# Memory_Address_Register.net
KiCad netlist of a schematic drawn in Altium Designer
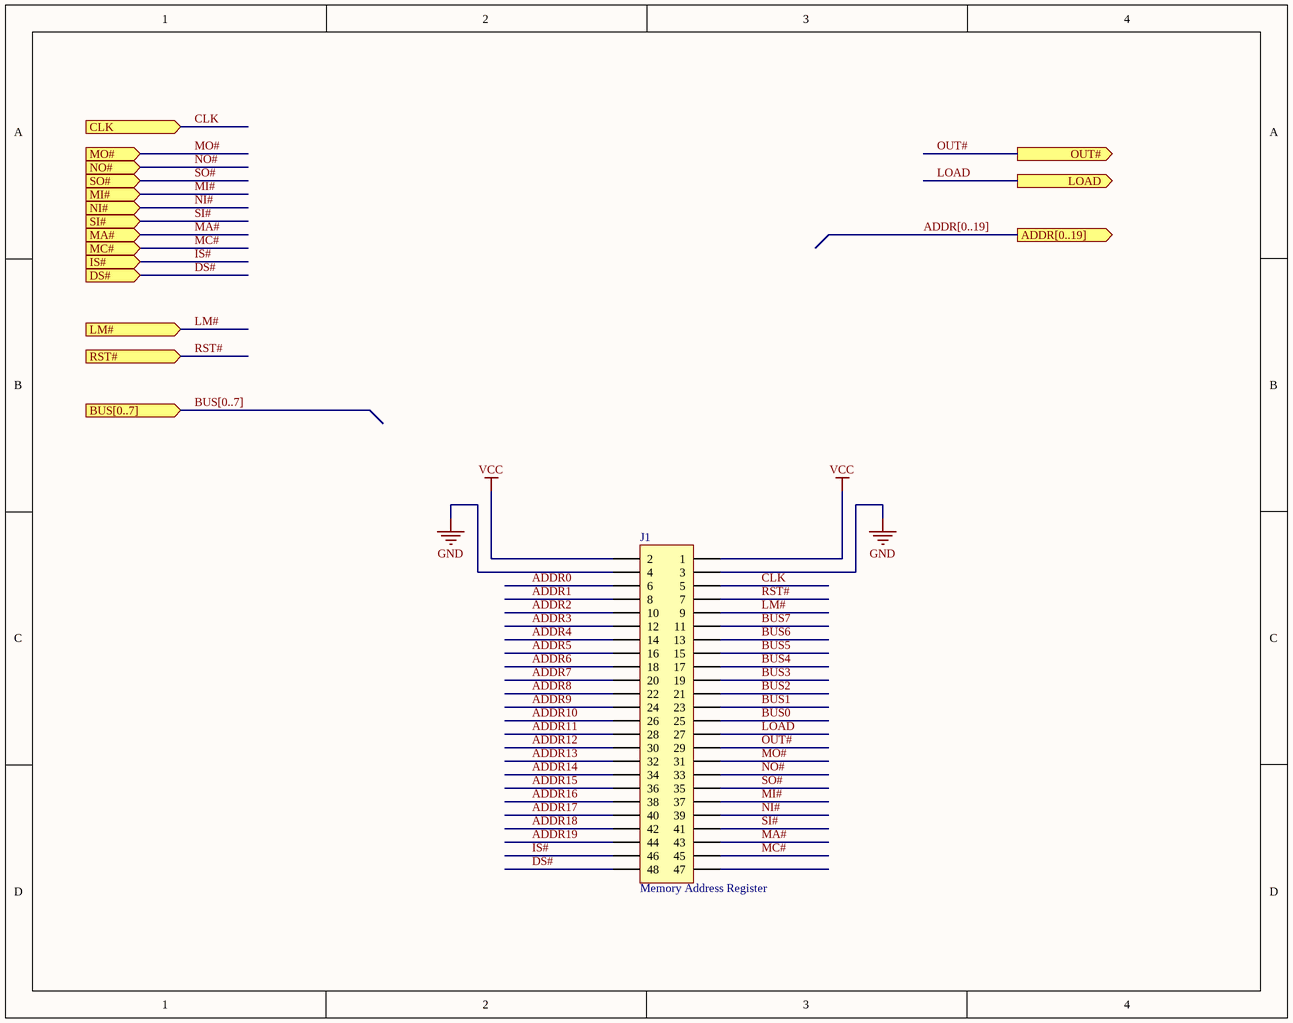
[diagram p0: Memory Address Register.SchDoc]

(export (version "E")
  (design (tool "Eeschema 10.0.6"))
  (components
    (comp (ref "J1")
      (value "Memory Address Register")
      (footprint "HDR2X24")
      (description "Header, 24-Pin, Dual row")
      (fields (field (name "PUBLISHER") "Altium Limited"))
      (libsource (lib "Miscellaneous Connectors") (part "Header 24X2"))
    )
  )
  (nets
    (net (code "1") (name "/ADDR0") (class "Default")
      (node (ref "J1") (pin "6") (pinfunction "6_6") (pintype "passive"))
    )
    (net (code "2") (name "/ADDR1") (class "Default")
      (node (ref "J1") (pin "8") (pinfunction "8_8") (pintype "passive"))
    )
    (net (code "3") (name "/ADDR2") (class "Default")
      (node (ref "J1") (pin "10") (pinfunction "10_10") (pintype "passive"))
    )
    (net (code "4") (name "/ADDR3") (class "Default")
      (node (ref "J1") (pin "12") (pinfunction "12_12") (pintype "passive"))
    )
    (net (code "5") (name "/ADDR4") (class "Default")
      (node (ref "J1") (pin "14") (pinfunction "14_14") (pintype "passive"))
    )
    (net (code "6") (name "/ADDR5") (class "Default")
      (node (ref "J1") (pin "16") (pinfunction "16_16") (pintype "passive"))
    )
    (net (code "7") (name "/ADDR6") (class "Default")
      (node (ref "J1") (pin "18") (pinfunction "18_18") (pintype "passive"))
    )
    (net (code "8") (name "/ADDR7") (class "Default")
      (node (ref "J1") (pin "20") (pinfunction "20_20") (pintype "passive"))
    )
    (net (code "9") (name "/ADDR8") (class "Default")
      (node (ref "J1") (pin "22") (pinfunction "22_22") (pintype "passive"))
    )
    (net (code "10") (name "/ADDR9") (class "Default")
      (node (ref "J1") (pin "24") (pinfunction "24_24") (pintype "passive"))
    )
    (net (code "11") (name "/ADDR10") (class "Default")
      (node (ref "J1") (pin "26") (pinfunction "26_26") (pintype "passive"))
    )
    (net (code "12") (name "/ADDR11") (class "Default")
      (node (ref "J1") (pin "28") (pinfunction "28_28") (pintype "passive"))
    )
    (net (code "13") (name "/ADDR12") (class "Default")
      (node (ref "J1") (pin "30") (pinfunction "30_30") (pintype "passive"))
    )
    (net (code "14") (name "/ADDR13") (class "Default")
      (node (ref "J1") (pin "32") (pinfunction "32_32") (pintype "passive"))
    )
    (net (code "15") (name "/ADDR14") (class "Default")
      (node (ref "J1") (pin "34") (pinfunction "34_34") (pintype "passive"))
    )
    (net (code "16") (name "/ADDR15") (class "Default")
      (node (ref "J1") (pin "36") (pinfunction "36_36") (pintype "passive"))
    )
    (net (code "17") (name "/ADDR16") (class "Default")
      (node (ref "J1") (pin "38") (pinfunction "38_38") (pintype "passive"))
    )
    (net (code "18") (name "/ADDR17") (class "Default")
      (node (ref "J1") (pin "40") (pinfunction "40_40") (pintype "passive"))
    )
    (net (code "19") (name "/ADDR18") (class "Default")
      (node (ref "J1") (pin "42") (pinfunction "42_42") (pintype "passive"))
    )
    (net (code "20") (name "/ADDR19") (class "Default")
      (node (ref "J1") (pin "44") (pinfunction "44_44") (pintype "passive"))
    )
    (net (code "22") (name "/BUS0") (class "Default")
      (node (ref "J1") (pin "25") (pinfunction "25_25") (pintype "passive"))
    )
    (net (code "23") (name "/BUS1") (class "Default")
      (node (ref "J1") (pin "23") (pinfunction "23_23") (pintype "passive"))
    )
    (net (code "24") (name "/BUS2") (class "Default")
      (node (ref "J1") (pin "21") (pinfunction "21_21") (pintype "passive"))
    )
    (net (code "25") (name "/BUS3") (class "Default")
      (node (ref "J1") (pin "19") (pinfunction "19_19") (pintype "passive"))
    )
    (net (code "26") (name "/BUS4") (class "Default")
      (node (ref "J1") (pin "17") (pinfunction "17_17") (pintype "passive"))
    )
    (net (code "27") (name "/BUS5") (class "Default")
      (node (ref "J1") (pin "15") (pinfunction "15_15") (pintype "passive"))
    )
    (net (code "28") (name "/BUS6") (class "Default")
      (node (ref "J1") (pin "13") (pinfunction "13_13") (pintype "passive"))
    )
    (net (code "29") (name "/BUS7") (class "Default")
      (node (ref "J1") (pin "11") (pinfunction "11_11") (pintype "passive"))
    )
    (net (code "31") (name "/CLK") (class "Default")
      (node (ref "J1") (pin "5") (pinfunction "5_5") (pintype "passive"))
    )
    (net (code "32") (name "/DS#") (class "Default")
      (node (ref "J1") (pin "48") (pinfunction "48_48") (pintype "passive"))
    )
    (net (code "33") (name "/IS#") (class "Default")
      (node (ref "J1") (pin "46") (pinfunction "46_46") (pintype "passive"))
    )
    (net (code "34") (name "/LM#") (class "Default")
      (node (ref "J1") (pin "9") (pinfunction "9_9") (pintype "passive"))
    )
    (net (code "35") (name "/LOAD") (class "Default")
      (node (ref "J1") (pin "27") (pinfunction "27_27") (pintype "passive"))
    )
    (net (code "36") (name "/MA#") (class "Default")
      (node (ref "J1") (pin "43") (pinfunction "43_43") (pintype "passive"))
    )
    (net (code "37") (name "/MC#") (class "Default")
      (node (ref "J1") (pin "45") (pinfunction "45_45") (pintype "passive"))
    )
    (net (code "38") (name "/MI#") (class "Default")
      (node (ref "J1") (pin "37") (pinfunction "37_37") (pintype "passive"))
    )
    (net (code "39") (name "/MO#") (class "Default")
      (node (ref "J1") (pin "31") (pinfunction "31_31") (pintype "passive"))
    )
    (net (code "40") (name "/NI#") (class "Default")
      (node (ref "J1") (pin "39") (pinfunction "39_39") (pintype "passive"))
    )
    (net (code "41") (name "/NO#") (class "Default")
      (node (ref "J1") (pin "33") (pinfunction "33_33") (pintype "passive"))
    )
    (net (code "42") (name "/OUT#") (class "Default")
      (node (ref "J1") (pin "29") (pinfunction "29_29") (pintype "passive"))
    )
    (net (code "43") (name "/RST#") (class "Default")
      (node (ref "J1") (pin "7") (pinfunction "7_7") (pintype "passive"))
    )
    (net (code "44") (name "/SI#") (class "Default")
      (node (ref "J1") (pin "41") (pinfunction "41_41") (pintype "passive"))
    )
    (net (code "45") (name "/SO#") (class "Default")
      (node (ref "J1") (pin "35") (pinfunction "35_35") (pintype "passive"))
    )
    (net (code "46") (name "GND") (class "Default")
      (node (ref "J1") (pin "3") (pinfunction "3_3") (pintype "passive"))
      (node (ref "J1") (pin "4") (pinfunction "4_4") (pintype "passive"))
    )
    (net (code "47") (name "VCC") (class "Default")
      (node (ref "J1") (pin "1") (pinfunction "1_1") (pintype "passive"))
      (node (ref "J1") (pin "2") (pinfunction "2_2") (pintype "passive"))
    )
    (net (code "48") (name "unconnected-(J1-Pad47)") (class "Default")
      (node (ref "J1") (pin "47") (pinfunction "47_47") (pintype "passive"))
    )
  )
)
